# Bus_Isolator.net
KiCad netlist of a schematic drawn in EAGLE
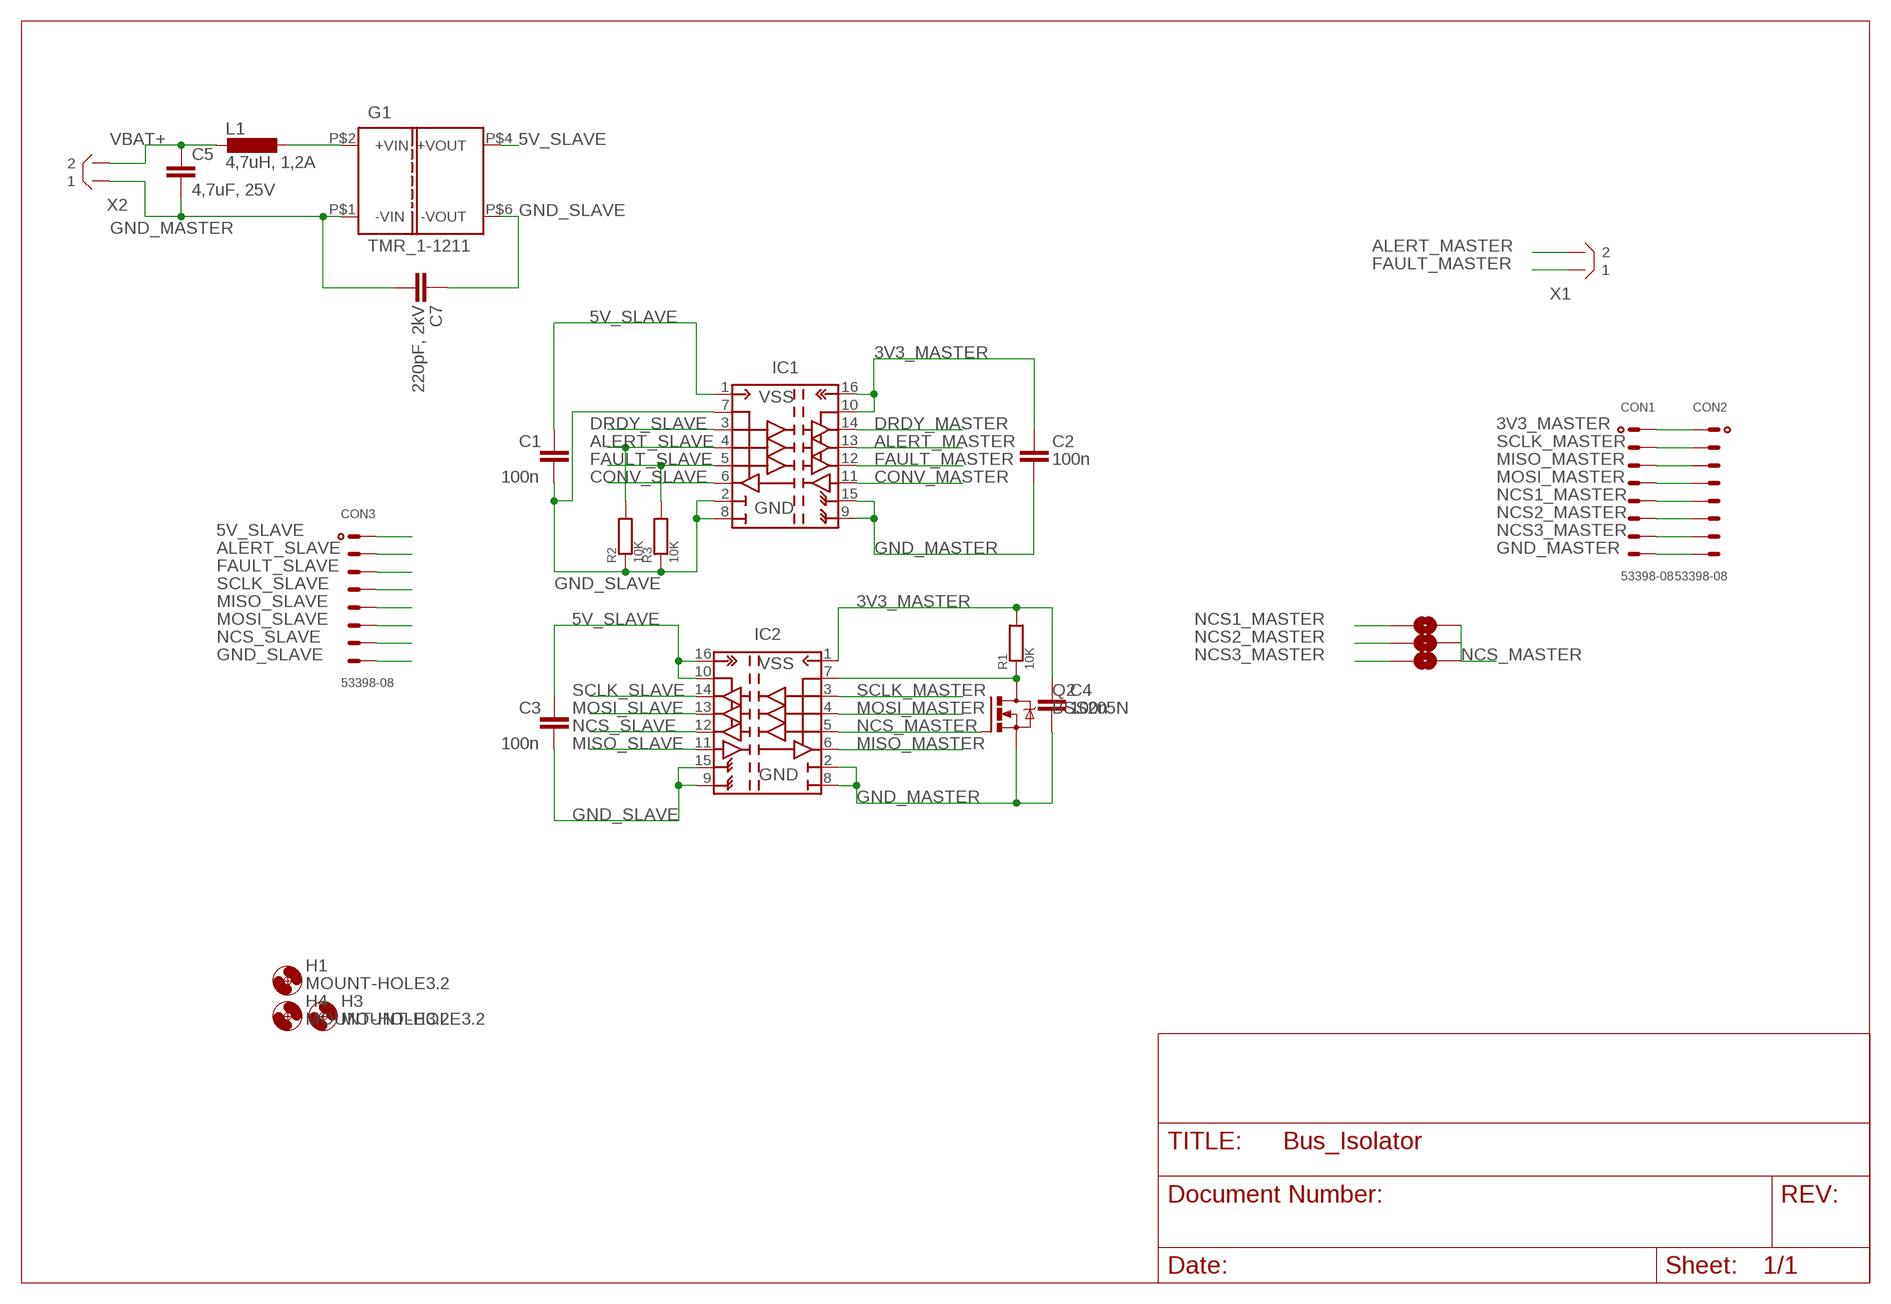
[diagram p0: schematic, sheet 1]

(export (version "E")
  (design (tool "Eeschema 10.0.6"))
  (components
    (comp (ref "C1")
      (value "100n")
      (footprint "eagle-import:C0805")
      (libsource (lib "eagle-import") (part "CSTD"))
    )
    (comp (ref "C2")
      (value "100n")
      (footprint "eagle-import:C0805")
      (libsource (lib "eagle-import") (part "CSTD"))
    )
    (comp (ref "C3")
      (value "100n")
      (footprint "eagle-import:C0805")
      (libsource (lib "eagle-import") (part "CSTD"))
    )
    (comp (ref "C4")
      (value "100n")
      (footprint "eagle-import:C0805")
      (libsource (lib "eagle-import") (part "CSTD"))
    )
    (comp (ref "C5")
      (value "4,7uF, 25V")
      (footprint "eagle-import:C0805")
      (libsource (lib "eagle-import") (part "C-EUC0805"))
    )
    (comp (ref "C7")
      (value "220pF, 2kV")
      (footprint "eagle-import:C1210_HV")
      (libsource (lib "eagle-import") (part "CC1210_HV"))
    )
    (comp (ref "CON1")
      (value "53398-08")
      (footprint "eagle-import:53398-08")
      (libsource (lib "eagle-import") (part "53?-08398"))
    )
    (comp (ref "CON2")
      (value "53398-08")
      (footprint "eagle-import:53398-08")
      (libsource (lib "eagle-import") (part "53?-08398"))
    )
    (comp (ref "CON3")
      (value "53398-08")
      (footprint "eagle-import:53398-08")
      (libsource (lib "eagle-import") (part "53?-08398"))
    )
    (comp (ref "G1")
      (value "TMR_1-1211")
      (footprint "eagle-import:TMR_1-__1_")
      (libsource (lib "eagle-import") (part "TMR_1-??1?"))
    )
    (comp (ref "H1")
      (value "MOUNT-HOLE3.2")
      (footprint "eagle-import:3,2")
      (libsource (lib "eagle-import") (part "MOUNT-HOLE3.2"))
    )
    (comp (ref "H3")
      (value "MOUNT-HOLE3.2")
      (footprint "eagle-import:3,2")
      (libsource (lib "eagle-import") (part "MOUNT-HOLE3.2"))
    )
    (comp (ref "H4")
      (value "MOUNT-HOLE3.2")
      (footprint "eagle-import:3,2")
      (libsource (lib "eagle-import") (part "MOUNT-HOLE3.2"))
    )
    (comp (ref "IC1")
      (value "ISO7241")
      (footprint "eagle-import:R-PDSO-G16")
      (libsource (lib "eagle-import") (part "ISO7241"))
    )
    (comp (ref "IC2")
      (value "ISO7241")
      (footprint "eagle-import:R-PDSO-G16")
      (libsource (lib "eagle-import") (part "ISO7241"))
    )
    (comp (ref "L1")
      (value "4,7uH, 1,2A")
      (footprint "eagle-import:L3225M")
      (libsource (lib "eagle-import") (part "L-EUL3225M"))
    )
    (comp (ref "Q2")
      (value "BSS205N")
      (footprint "eagle-import:SOT23")
      (libsource (lib "eagle-import") (part "BSS205N"))
    )
    (comp (ref "R1")
      (value "10K")
      (footprint "eagle-import:R0805")
      (libsource (lib "eagle-import") (part "R"))
    )
    (comp (ref "R2")
      (value "10K")
      (footprint "eagle-import:R0805")
      (libsource (lib "eagle-import") (part "R"))
    )
    (comp (ref "R3")
      (value "10K")
      (footprint "eagle-import:R0805")
      (libsource (lib "eagle-import") (part "R"))
    )
    (comp (ref "SJ1")
      (value "SOLDERJUMPERNO")
      (footprint "eagle-import:SJ_2S-NO")
      (libsource (lib "eagle-import") (part "SOLDERJUMPERNO"))
    )
    (comp (ref "SJ2")
      (value "SOLDERJUMPERNO")
      (footprint "eagle-import:SJ_2S-NO")
      (libsource (lib "eagle-import") (part "SOLDERJUMPERNO"))
    )
    (comp (ref "SJ4")
      (value "SOLDERJUMPERNO")
      (footprint "eagle-import:SJ_2S-NO")
      (libsource (lib "eagle-import") (part "SOLDERJUMPERNO"))
    )
    (comp (ref "X1")
      (value "B2B-XH")
      (footprint "eagle-import:B2B-XH")
      (libsource (lib "eagle-import") (part "?2B-XHB"))
    )
    (comp (ref "X2")
      (value "B2B-XH")
      (footprint "eagle-import:B2B-XH")
      (libsource (lib "eagle-import") (part "?2B-XHB"))
    )
  )
  (nets
    (net (code "1") (name "/3V3_MASTER") (class "Default")
      (node (ref "C2") (pin "2") (pinfunction "2_2") (pintype "passive"))
      (node (ref "C4") (pin "2") (pinfunction "2_2") (pintype "passive"))
      (node (ref "CON1") (pin "1") (pinfunction "1_1") (pintype "passive"))
      (node (ref "CON2") (pin "1") (pinfunction "1_1") (pintype "passive"))
      (node (ref "IC1") (pin "10") (pinfunction "EN2_10") (pintype "bidirectional"))
      (node (ref "IC1") (pin "16") (pinfunction "VCC2_16") (pintype "bidirectional"))
      (node (ref "IC2") (pin "1") (pinfunction "VCC1_1") (pintype "bidirectional"))
      (node (ref "R1") (pin "2") (pinfunction "2_2") (pintype "passive"))
    )
    (net (code "2") (name "/5V_SLAVE") (class "Default")
      (node (ref "C1") (pin "2") (pinfunction "2_2") (pintype "passive"))
      (node (ref "C3") (pin "2") (pinfunction "2_2") (pintype "passive"))
      (node (ref "CON3") (pin "1") (pinfunction "1_1") (pintype "passive"))
      (node (ref "G1") (pin "P$4") (pinfunction "+VOUT_P$4") (pintype "bidirectional"))
      (node (ref "IC1") (pin "1") (pinfunction "VCC1_1") (pintype "bidirectional"))
      (node (ref "IC2") (pin "10") (pinfunction "EN2_10") (pintype "bidirectional"))
      (node (ref "IC2") (pin "16") (pinfunction "VCC2_16") (pintype "bidirectional"))
    )
    (net (code "3") (name "/ALERT_MASTER") (class "Default")
      (node (ref "IC1") (pin "13") (pinfunction "OUT_B_13") (pintype "bidirectional"))
      (node (ref "X1") (pin "P$2") (pinfunction "2_P$2") (pintype "bidirectional"))
    )
    (net (code "4") (name "/ALERT_SLAVE") (class "Default")
      (node (ref "CON3") (pin "2") (pinfunction "2_2") (pintype "passive"))
      (node (ref "IC1") (pin "4") (pinfunction "IN_B_4") (pintype "bidirectional"))
      (node (ref "R2") (pin "2") (pinfunction "2_2") (pintype "passive"))
    )
    (net (code "5") (name "/CONV_MASTER") (class "Default")
      (node (ref "IC1") (pin "11") (pinfunction "IN_D_11") (pintype "bidirectional"))
    )
    (net (code "6") (name "/CONV_SLAVE") (class "Default")
      (node (ref "IC1") (pin "6") (pinfunction "OUT_D_6") (pintype "bidirectional"))
    )
    (net (code "7") (name "/DRDY_MASTER") (class "Default")
      (node (ref "IC1") (pin "14") (pinfunction "OUT_A_14") (pintype "bidirectional"))
    )
    (net (code "8") (name "/DRDY_SLAVE") (class "Default")
      (node (ref "IC1") (pin "3") (pinfunction "IN_A_3") (pintype "bidirectional"))
    )
    (net (code "9") (name "/FAULT_MASTER") (class "Default")
      (node (ref "IC1") (pin "12") (pinfunction "OUT_C_12") (pintype "bidirectional"))
      (node (ref "X1") (pin "P$1") (pinfunction "1_P$1") (pintype "bidirectional"))
    )
    (net (code "10") (name "/FAULT_SLAVE") (class "Default")
      (node (ref "CON3") (pin "3") (pinfunction "3_3") (pintype "passive"))
      (node (ref "IC1") (pin "5") (pinfunction "IN_C_5") (pintype "bidirectional"))
      (node (ref "R3") (pin "2") (pinfunction "2_2") (pintype "passive"))
    )
    (net (code "11") (name "/GND_MASTER") (class "Default")
      (node (ref "C2") (pin "1") (pinfunction "1_1") (pintype "passive"))
      (node (ref "C4") (pin "1") (pinfunction "1_1") (pintype "passive"))
      (node (ref "C5") (pin "2") (pinfunction "2_2") (pintype "passive"))
      (node (ref "C7") (pin "P$1") (pinfunction "1_P$1") (pintype "passive"))
      (node (ref "CON1") (pin "8") (pinfunction "8_8") (pintype "passive"))
      (node (ref "CON2") (pin "8") (pinfunction "8_8") (pintype "passive"))
      (node (ref "G1") (pin "P$1") (pinfunction "-VIN_P$1") (pintype "bidirectional"))
      (node (ref "IC1") (pin "15") (pinfunction "GND21_15") (pintype "bidirectional"))
      (node (ref "IC1") (pin "9") (pinfunction "GND22_9") (pintype "bidirectional"))
      (node (ref "IC2") (pin "2") (pinfunction "GND11_2") (pintype "bidirectional"))
      (node (ref "IC2") (pin "8") (pinfunction "GND12_8") (pintype "bidirectional"))
      (node (ref "Q2") (pin "2") (pinfunction "S_2") (pintype "passive"))
      (node (ref "X2") (pin "P$1") (pinfunction "1_P$1") (pintype "bidirectional"))
    )
    (net (code "12") (name "/GND_SLAVE") (class "Default")
      (node (ref "C1") (pin "1") (pinfunction "1_1") (pintype "passive"))
      (node (ref "C3") (pin "1") (pinfunction "1_1") (pintype "passive"))
      (node (ref "C7") (pin "P$2") (pinfunction "2_P$2") (pintype "passive"))
      (node (ref "CON3") (pin "8") (pinfunction "8_8") (pintype "passive"))
      (node (ref "G1") (pin "P$6") (pinfunction "-VOUT_P$6") (pintype "bidirectional"))
      (node (ref "IC1") (pin "2") (pinfunction "GND11_2") (pintype "bidirectional"))
      (node (ref "IC1") (pin "7") (pinfunction "EN1_7") (pintype "bidirectional"))
      (node (ref "IC1") (pin "8") (pinfunction "GND12_8") (pintype "bidirectional"))
      (node (ref "IC2") (pin "15") (pinfunction "GND21_15") (pintype "bidirectional"))
      (node (ref "IC2") (pin "9") (pinfunction "GND22_9") (pintype "bidirectional"))
      (node (ref "R2") (pin "1") (pinfunction "1_1") (pintype "passive"))
      (node (ref "R3") (pin "1") (pinfunction "1_1") (pintype "passive"))
    )
    (net (code "13") (name "/MISO_MASTER") (class "Default")
      (node (ref "CON1") (pin "3") (pinfunction "3_3") (pintype "passive"))
      (node (ref "CON2") (pin "3") (pinfunction "3_3") (pintype "passive"))
      (node (ref "IC2") (pin "6") (pinfunction "OUT_D_6") (pintype "bidirectional"))
    )
    (net (code "14") (name "/MISO_SLAVE") (class "Default")
      (node (ref "CON3") (pin "5") (pinfunction "5_5") (pintype "passive"))
      (node (ref "IC2") (pin "11") (pinfunction "IN_D_11") (pintype "bidirectional"))
    )
    (net (code "15") (name "/MOSI_MASTER") (class "Default")
      (node (ref "CON1") (pin "4") (pinfunction "4_4") (pintype "passive"))
      (node (ref "CON2") (pin "4") (pinfunction "4_4") (pintype "passive"))
      (node (ref "IC2") (pin "4") (pinfunction "IN_B_4") (pintype "bidirectional"))
    )
    (net (code "16") (name "/MOSI_SLAVE") (class "Default")
      (node (ref "CON3") (pin "6") (pinfunction "6_6") (pintype "passive"))
      (node (ref "IC2") (pin "13") (pinfunction "OUT_B_13") (pintype "bidirectional"))
    )
    (net (code "17") (name "/NCS1_MASTER") (class "Default")
      (node (ref "CON1") (pin "5") (pinfunction "5_5") (pintype "passive"))
      (node (ref "CON2") (pin "5") (pinfunction "5_5") (pintype "passive"))
      (node (ref "SJ1") (pin "1") (pinfunction "1_1") (pintype "passive"))
    )
    (net (code "18") (name "/NCS2_MASTER") (class "Default")
      (node (ref "CON1") (pin "6") (pinfunction "6_6") (pintype "passive"))
      (node (ref "CON2") (pin "6") (pinfunction "6_6") (pintype "passive"))
      (node (ref "SJ2") (pin "1") (pinfunction "1_1") (pintype "passive"))
    )
    (net (code "19") (name "/NCS3_MASTER") (class "Default")
      (node (ref "CON1") (pin "7") (pinfunction "7_7") (pintype "passive"))
      (node (ref "CON2") (pin "7") (pinfunction "7_7") (pintype "passive"))
      (node (ref "SJ4") (pin "1") (pinfunction "1_1") (pintype "passive"))
    )
    (net (code "20") (name "/NCS_MASTER") (class "Default")
      (node (ref "IC2") (pin "5") (pinfunction "IN_C_5") (pintype "bidirectional"))
      (node (ref "Q2") (pin "1") (pinfunction "G_1") (pintype "passive"))
      (node (ref "SJ1") (pin "2") (pinfunction "2_2") (pintype "passive"))
      (node (ref "SJ2") (pin "2") (pinfunction "2_2") (pintype "passive"))
      (node (ref "SJ4") (pin "2") (pinfunction "2_2") (pintype "passive"))
    )
    (net (code "21") (name "/NCS_SLAVE") (class "Default")
      (node (ref "CON3") (pin "7") (pinfunction "7_7") (pintype "passive"))
      (node (ref "IC2") (pin "12") (pinfunction "OUT_C_12") (pintype "bidirectional"))
    )
    (net (code "22") (name "/SCLK_MASTER") (class "Default")
      (node (ref "CON1") (pin "2") (pinfunction "2_2") (pintype "passive"))
      (node (ref "CON2") (pin "2") (pinfunction "2_2") (pintype "passive"))
      (node (ref "IC2") (pin "3") (pinfunction "IN_A_3") (pintype "bidirectional"))
    )
    (net (code "23") (name "/SCLK_SLAVE") (class "Default")
      (node (ref "CON3") (pin "4") (pinfunction "4_4") (pintype "passive"))
      (node (ref "IC2") (pin "14") (pinfunction "OUT_A_14") (pintype "bidirectional"))
    )
    (net (code "24") (name "/VBAT+") (class "Default")
      (node (ref "C5") (pin "1") (pinfunction "1_1") (pintype "passive"))
      (node (ref "L1") (pin "2") (pinfunction "2_2") (pintype "passive"))
      (node (ref "X2") (pin "P$2") (pinfunction "2_P$2") (pintype "bidirectional"))
    )
    (net (code "25") (name "Net-(G1-+VIN)") (class "Default")
      (node (ref "G1") (pin "P$2") (pinfunction "+VIN_P$2") (pintype "bidirectional"))
      (node (ref "L1") (pin "1") (pinfunction "1_1") (pintype "passive"))
    )
    (net (code "26") (name "Net-(IC2-EN1)") (class "Default")
      (node (ref "IC2") (pin "7") (pinfunction "EN1_7") (pintype "bidirectional"))
      (node (ref "Q2") (pin "3") (pinfunction "D_3") (pintype "passive"))
      (node (ref "R1") (pin "1") (pinfunction "1_1") (pintype "passive"))
    )
  )
)
